# MicroSD.net
KiCad netlist of a schematic drawn in Altium Designer
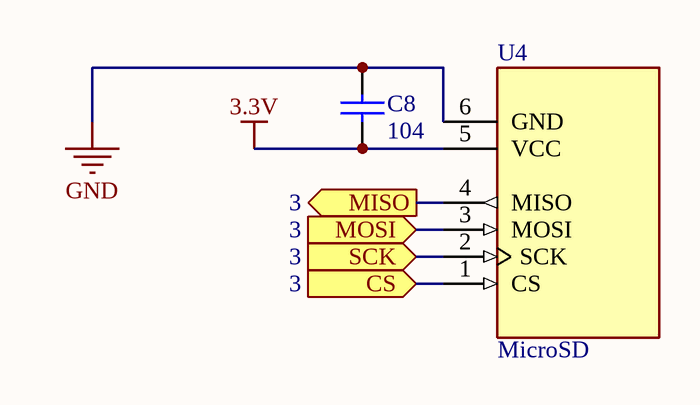
[diagram p0: MicroSD.SchDoc]

(export (version "E")
  (design (tool "Eeschema 10.0.6"))
  (components
    (comp (ref "C8")
      (value "104")
      (footprint "tu gom")
      (description "Cắm")
      (libsource (lib "Altium_Lib_by_KhueNguyenCreator") (part "Tu gom 104 50V"))
    )
    (comp (ref "U4")
      (value "MicroSD")
      (footprint "MODULE_254")
      (description "MicroSD card breakout board+")
      (fields (field (name "MF") "Keystone Electronics") (field (name "MP") "254"))
      (libsource (lib "microSD") (part "254"))
    )
  )
  (nets
    (net (code "1") (name "/CS") (class "Default")
      (node (ref "U4") (pin "1") (pinfunction "CS_1") (pintype "input"))
    )
    (net (code "2") (name "/MISO") (class "Default")
      (node (ref "U4") (pin "4") (pinfunction "MISO_4") (pintype "output"))
    )
    (net (code "3") (name "/MOSI") (class "Default")
      (node (ref "U4") (pin "3") (pinfunction "MOSI_3") (pintype "input"))
    )
    (net (code "4") (name "/SCK") (class "Default")
      (node (ref "U4") (pin "2") (pinfunction "SCK_2") (pintype "input"))
    )
    (net (code "5") (name "3.3V") (class "Default")
      (node (ref "C8") (pin "2") (pinfunction "2_2") (pintype "passive"))
      (node (ref "U4") (pin "5") (pinfunction "VCC_5") (pintype "power_in"))
    )
    (net (code "6") (name "GND") (class "Default")
      (node (ref "C8") (pin "1") (pinfunction "1_1") (pintype "passive"))
      (node (ref "U4") (pin "6") (pinfunction "GND_6") (pintype "power_in"))
    )
  )
)
